# MCU.net
KiCad netlist of a schematic drawn in Altium Designer
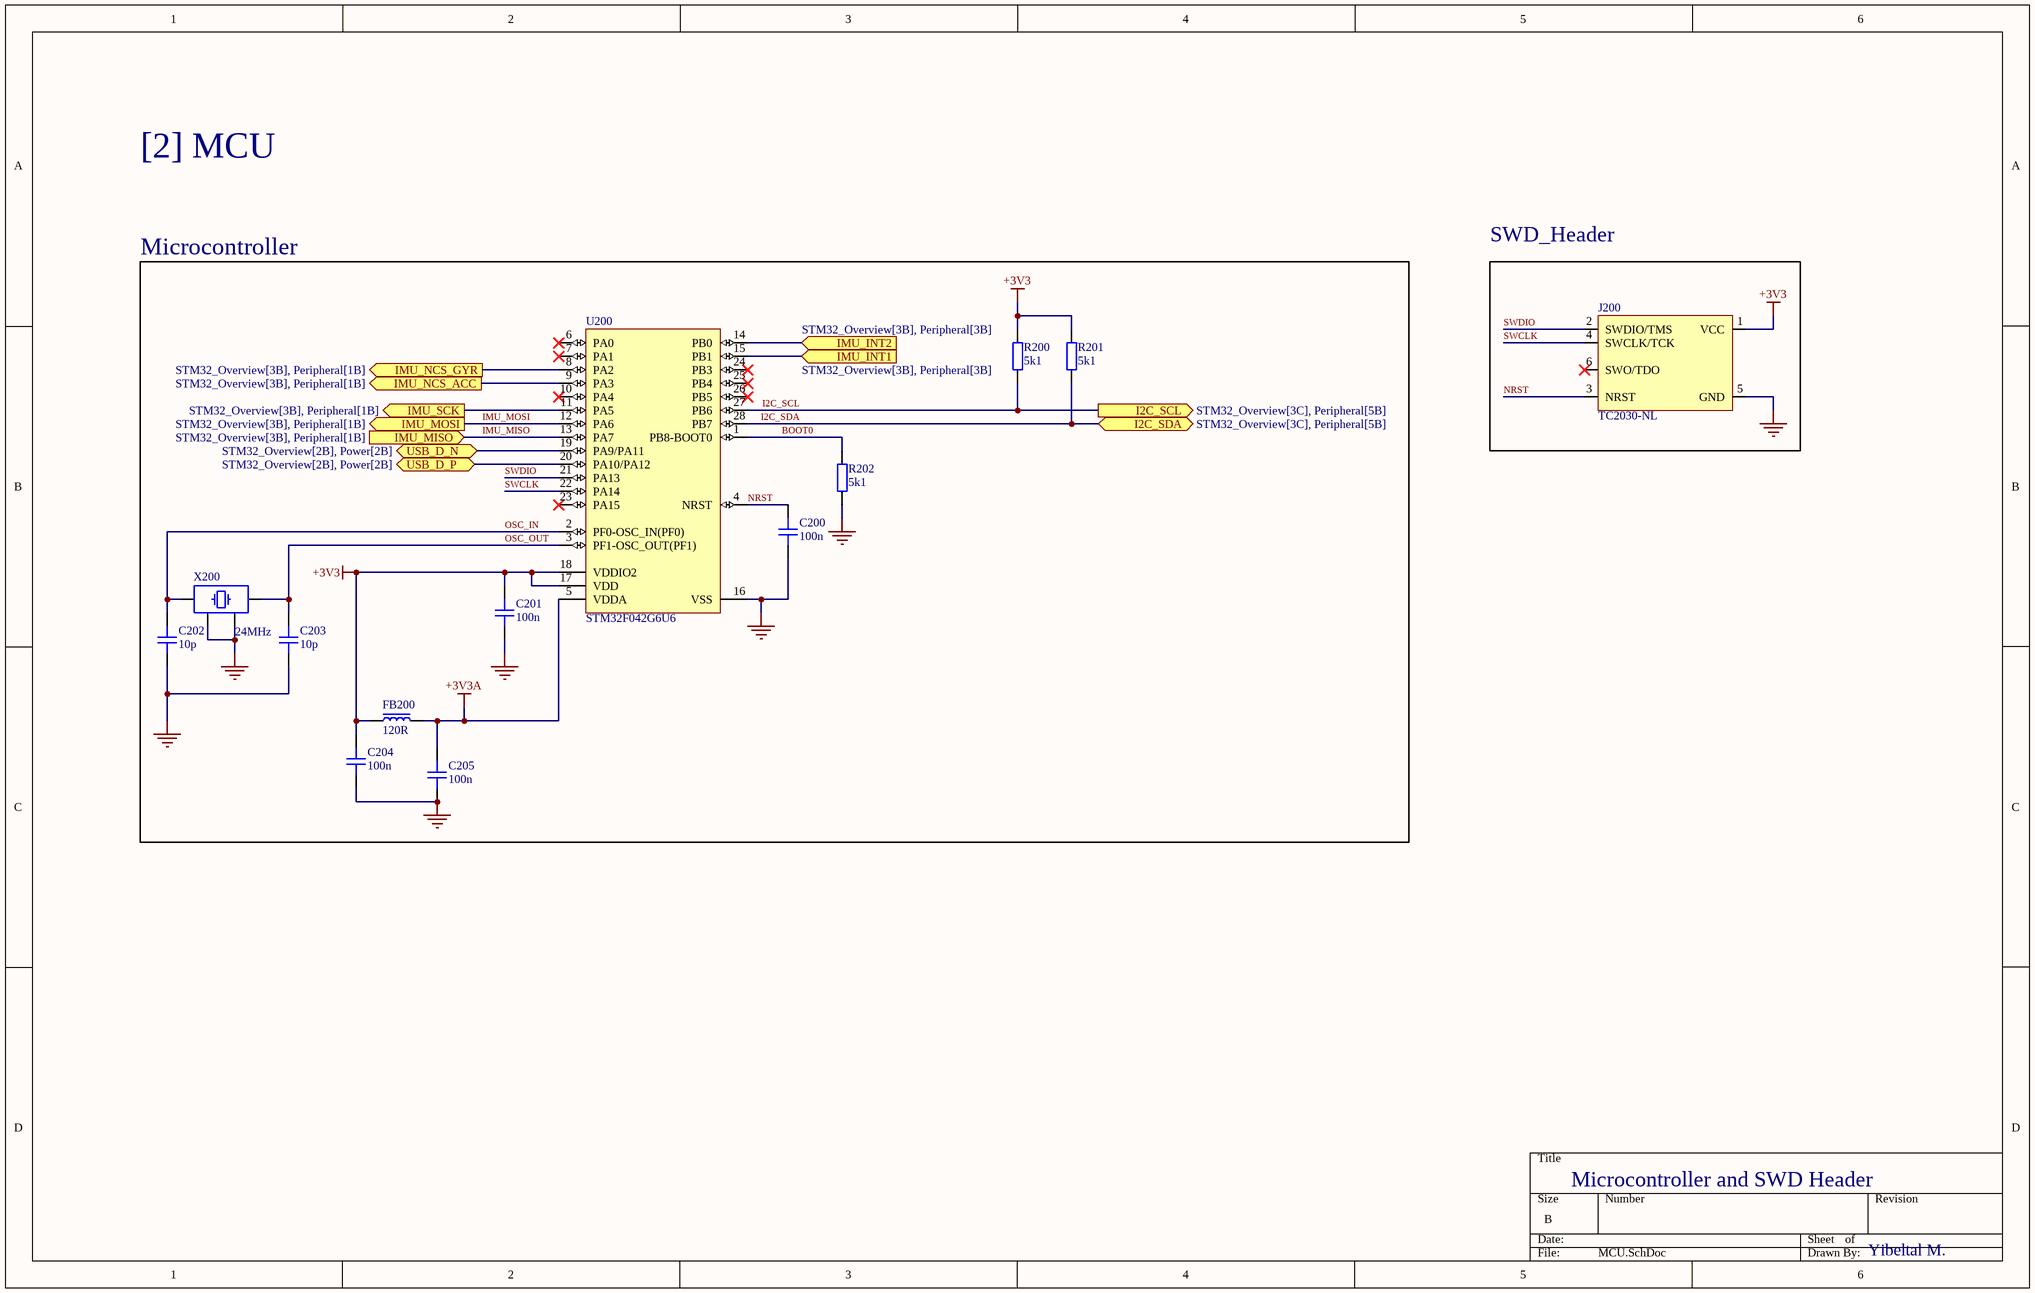
[diagram p0: MCU.SchDoc]

(export (version "E")
  (design (tool "Eeschema 10.0.6"))
  (components
    (comp (ref "C200")
      (value "100n")
      (footprint "CAP_0805")
      (description "Capacitor SMD 0805")
      (libsource (lib "Schematic-Lib-PhilsLab (2)") (part "CAP_0805"))
    )
    (comp (ref "C201")
      (value "100n")
      (footprint "CAP_0805")
      (description "Capacitor SMD 0805")
      (libsource (lib "Schematic-Lib-PhilsLab (2)") (part "CAP_0805"))
    )
    (comp (ref "C202")
      (value "10p")
      (footprint "CAP_0805")
      (description "Capacitor SMD 0805")
      (libsource (lib "Schematic-Lib-PhilsLab (2)") (part "CAP_0805"))
    )
    (comp (ref "C203")
      (value "10p")
      (footprint "CAP_0805")
      (description "Capacitor SMD 0805")
      (libsource (lib "Schematic-Lib-PhilsLab (2)") (part "CAP_0805"))
    )
    (comp (ref "C204")
      (value "100n")
      (footprint "CAP_0805")
      (description "Capacitor SMD 0805")
      (libsource (lib "Schematic-Lib-PhilsLab (2)") (part "CAP_0805"))
    )
    (comp (ref "C205")
      (value "100n")
      (footprint "CAP_0805")
      (description "Capacitor SMD 0805")
      (libsource (lib "Schematic-Lib-PhilsLab (2)") (part "CAP_0805"))
    )
    (comp (ref "FB200")
      (value "120R")
      (footprint "FB_0603")
      (description "Ferrite Bead SMD 0603")
      (libsource (lib "Schematic-Lib-PhilsLab (2)") (part "FB_0603"))
    )
    (comp (ref "J200")
      (value "TC2030-NL")
      (footprint "TC2030-NL-FP")
      (description "Tag-Connect No-Solder SWD Debug Connector (No Legs) DO NOT PLACE")
      (fields
        (field (name "MANUFACTURER") "Tag-Connect")
        (field (name "MANUFACTURER PART NUMBER") "TC2030-NL-FP")
      )
      (libsource (lib "Schematic-Lib-PhilsLab (2)") (part "TC2030-NL"))
    )
    (comp (ref "R200")
      (value "5k1")
      (footprint "RES_0603")
      (description "Resistor SMD 0603")
      (libsource (lib "Schematic-Lib-PhilsLab (2)") (part "RES_0603"))
    )
    (comp (ref "R201")
      (value "5k1")
      (footprint "RES_0603")
      (description "Resistor SMD 0603")
      (libsource (lib "Schematic-Lib-PhilsLab (2)") (part "RES_0603"))
    )
    (comp (ref "R202")
      (value "5k1")
      (footprint "RES_0603")
      (description "Resistor SMD 0603")
      (libsource (lib "Schematic-Lib-PhilsLab (2)") (part "RES_0603"))
    )
    (comp (ref "U200")
      (value "STM32F042G6U6")
      (footprint "STM-UFQFPN28_V")
      (fields (field (name "MANUFACTURER") "STMicroelectronics"))
      (libsource (lib "Altium Content Vault") (part "MC-ARM-STM32F042-UFQFPN28"))
    )
    (comp (ref "X200")
      (value "24MHz")
      (footprint "XTAL_3225")
      (description "Crystal SMD 24MHz 10PPM 7pF 3225")
      (fields
        (field (name "MANUFACTURER") "Epson")
        (field (name "MANUFACTURER PART NUMBER") "TSX-3225 24.0000MF15X-AC")
      )
      (libsource (lib "Schematic-Lib-PhilsLab (2)") (part "TSX-3225_24.0000MF15X-AC"))
    )
  )
  (nets
    (net (code "1") (name "+3V3") (class "Default")
      (node (ref "C201") (pin "2") (pinfunction "2_2") (pintype "passive"))
      (node (ref "C204") (pin "2") (pinfunction "2_2") (pintype "passive"))
      (node (ref "FB200") (pin "1") (pinfunction "1_1") (pintype "passive"))
      (node (ref "J200") (pin "1") (pinfunction "VCC_1") (pintype "passive"))
      (node (ref "R200") (pin "2") (pinfunction "2_2") (pintype "passive"))
      (node (ref "R201") (pin "2") (pinfunction "2_2") (pintype "passive"))
      (node (ref "U200") (pin "17") (pinfunction "VDD_17") (pintype "power_in"))
      (node (ref "U200") (pin "18") (pinfunction "VDDIO2_18") (pintype "power_in"))
    )
    (net (code "2") (name "+3V3A") (class "Default")
      (node (ref "C205") (pin "2") (pinfunction "2_2") (pintype "passive"))
      (node (ref "FB200") (pin "2") (pinfunction "2_2") (pintype "passive"))
      (node (ref "U200") (pin "5") (pinfunction "VDDA_5") (pintype "power_in"))
    )
    (net (code "3") (name "/BOOT0") (class "Default")
      (node (ref "R202") (pin "2") (pinfunction "2_2") (pintype "passive"))
      (node (ref "U200") (pin "1") (pinfunction "PB8-BOOT0_1") (pintype "bidirectional"))
    )
    (net (code "4") (name "/I2C_SCL") (class "Default")
      (node (ref "R200") (pin "1") (pinfunction "1_1") (pintype "passive"))
      (node (ref "U200") (pin "27") (pinfunction "PB6_27") (pintype "bidirectional"))
    )
    (net (code "5") (name "/I2C_SDA") (class "Default")
      (node (ref "R201") (pin "1") (pinfunction "1_1") (pintype "passive"))
      (node (ref "U200") (pin "28") (pinfunction "PB7_28") (pintype "bidirectional"))
    )
    (net (code "6") (name "/IMU_INT1") (class "Default")
      (node (ref "U200") (pin "15") (pinfunction "PB1_15") (pintype "bidirectional"))
    )
    (net (code "7") (name "/IMU_INT2") (class "Default")
      (node (ref "U200") (pin "14") (pinfunction "PB0_14") (pintype "bidirectional"))
    )
    (net (code "8") (name "/IMU_MISO") (class "Default")
      (node (ref "U200") (pin "13") (pinfunction "PA7_13") (pintype "bidirectional"))
    )
    (net (code "9") (name "/IMU_MOSI") (class "Default")
      (node (ref "U200") (pin "12") (pinfunction "PA6_12") (pintype "bidirectional"))
    )
    (net (code "10") (name "/IMU_NCS_ACC") (class "Default")
      (node (ref "U200") (pin "9") (pinfunction "PA3_9") (pintype "bidirectional"))
    )
    (net (code "11") (name "/IMU_NCS_GYR") (class "Default")
      (node (ref "U200") (pin "8") (pinfunction "PA2_8") (pintype "bidirectional"))
    )
    (net (code "12") (name "/IMU_SCK") (class "Default")
      (node (ref "U200") (pin "11") (pinfunction "PA5_11") (pintype "bidirectional"))
    )
    (net (code "13") (name "/NRST") (class "Default")
      (node (ref "C200") (pin "2") (pinfunction "2_2") (pintype "passive"))
      (node (ref "J200") (pin "3") (pinfunction "NRST_3") (pintype "passive"))
      (node (ref "U200") (pin "4") (pinfunction "NRST_4") (pintype "bidirectional"))
    )
    (net (code "14") (name "/OSC_IN") (class "Default")
      (node (ref "C202") (pin "2") (pinfunction "2_2") (pintype "passive"))
      (node (ref "U200") (pin "2") (pinfunction "PF0-OSC_IN(PF0)_2") (pintype "bidirectional"))
      (node (ref "X200") (pin "1") (pinfunction "1_1") (pintype "passive"))
    )
    (net (code "15") (name "/OSC_OUT") (class "Default")
      (node (ref "C203") (pin "2") (pinfunction "2_2") (pintype "passive"))
      (node (ref "U200") (pin "3") (pinfunction "PF1-OSC_OUT(PF1)_3") (pintype "bidirectional"))
      (node (ref "X200") (pin "3") (pinfunction "3_3") (pintype "passive"))
    )
    (net (code "16") (name "/SWCLK") (class "Default")
      (node (ref "J200") (pin "4") (pinfunction "SWCLK/TCK_4") (pintype "passive"))
      (node (ref "U200") (pin "22") (pinfunction "PA14_22") (pintype "bidirectional"))
    )
    (net (code "17") (name "/SWDIO") (class "Default")
      (node (ref "J200") (pin "2") (pinfunction "SWDIO/TMS_2") (pintype "passive"))
      (node (ref "U200") (pin "21") (pinfunction "PA13_21") (pintype "bidirectional"))
    )
    (net (code "18") (name "/USB_D_N") (class "Default")
      (node (ref "U200") (pin "19") (pinfunction "PA9/PA11_19") (pintype "bidirectional"))
    )
    (net (code "19") (name "/USB_D_P") (class "Default")
      (node (ref "U200") (pin "20") (pinfunction "PA10/PA12_20") (pintype "bidirectional"))
    )
    (net (code "20") (name "GND") (class "Default")
      (node (ref "C200") (pin "1") (pinfunction "1_1") (pintype "passive"))
      (node (ref "C201") (pin "1") (pinfunction "1_1") (pintype "passive"))
      (node (ref "C202") (pin "1") (pinfunction "1_1") (pintype "passive"))
      (node (ref "C203") (pin "1") (pinfunction "1_1") (pintype "passive"))
      (node (ref "C204") (pin "1") (pinfunction "1_1") (pintype "passive"))
      (node (ref "C205") (pin "1") (pinfunction "1_1") (pintype "passive"))
      (node (ref "J200") (pin "5") (pinfunction "GND_5") (pintype "passive"))
      (node (ref "R202") (pin "1") (pinfunction "1_1") (pintype "passive"))
      (node (ref "U200") (pin "16") (pinfunction "VSS_16") (pintype "power_in"))
      (node (ref "X200") (pin "2") (pinfunction "2_2") (pintype "passive"))
      (node (ref "X200") (pin "4") (pinfunction "4_4") (pintype "passive"))
    )
    (net (code "21") (name "unconnected-(J200-SWO{slash}TDO-Pad6)") (class "Default")
      (node (ref "J200") (pin "6") (pinfunction "SWO/TDO_6") (pintype "passive+no_connect"))
    )
    (net (code "22") (name "unconnected-(U200-PA0-Pad6)") (class "Default")
      (node (ref "U200") (pin "6") (pinfunction "PA0_6") (pintype "bidirectional+no_connect"))
    )
    (net (code "23") (name "unconnected-(U200-PA1-Pad7)") (class "Default")
      (node (ref "U200") (pin "7") (pinfunction "PA1_7") (pintype "bidirectional+no_connect"))
    )
    (net (code "24") (name "unconnected-(U200-PA4-Pad10)") (class "Default")
      (node (ref "U200") (pin "10") (pinfunction "PA4_10") (pintype "bidirectional+no_connect"))
    )
    (net (code "25") (name "unconnected-(U200-PA15-Pad23)") (class "Default")
      (node (ref "U200") (pin "23") (pinfunction "PA15_23") (pintype "bidirectional+no_connect"))
    )
    (net (code "26") (name "unconnected-(U200-PB3-Pad24)") (class "Default")
      (node (ref "U200") (pin "24") (pinfunction "PB3_24") (pintype "bidirectional+no_connect"))
    )
    (net (code "27") (name "unconnected-(U200-PB4-Pad25)") (class "Default")
      (node (ref "U200") (pin "25") (pinfunction "PB4_25") (pintype "bidirectional+no_connect"))
    )
    (net (code "28") (name "unconnected-(U200-PB5-Pad26)") (class "Default")
      (node (ref "U200") (pin "26") (pinfunction "PB5_26") (pintype "bidirectional+no_connect"))
    )
  )
)
